# DataBreak.net
KiCad netlist of a schematic drawn in EAGLE
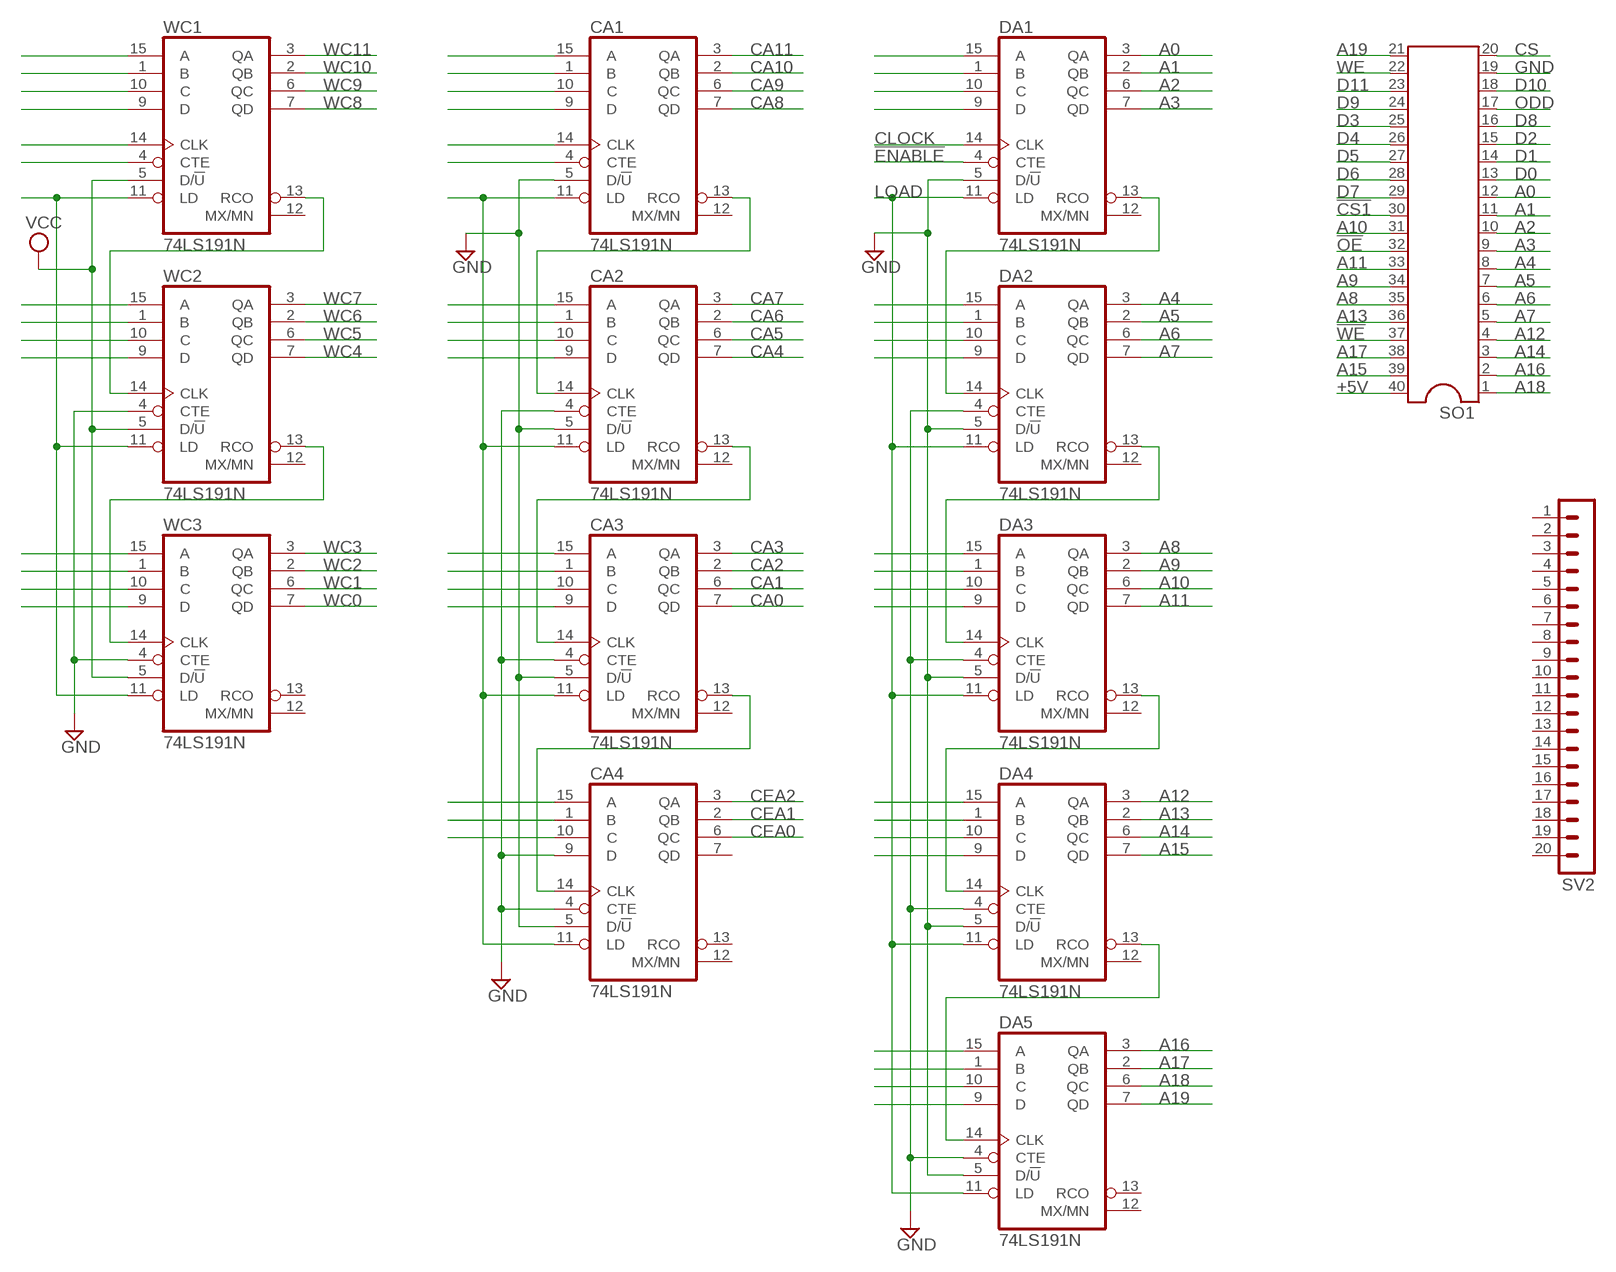
[diagram p0: schematic, sheet 1]

(export (version "E")
  (design (tool "Eeschema 10.0.6"))
  (components
    (comp (ref "CA1")
      (value "74LS191N")
      (footprint "eagle-import:DIL16")
      (libsource (lib "eagle-import") (part "74190NLS"))
    )
    (comp (ref "CA2")
      (value "74LS191N")
      (footprint "eagle-import:DIL16")
      (libsource (lib "eagle-import") (part "74190NLS"))
    )
    (comp (ref "CA3")
      (value "74LS191N")
      (footprint "eagle-import:DIL16")
      (libsource (lib "eagle-import") (part "74190NLS"))
    )
    (comp (ref "CA4")
      (value "74LS191N")
      (footprint "eagle-import:DIL16")
      (libsource (lib "eagle-import") (part "74190NLS"))
    )
    (comp (ref "DA1")
      (value "74LS191N")
      (footprint "eagle-import:DIL16")
      (libsource (lib "eagle-import") (part "74190NLS"))
    )
    (comp (ref "DA2")
      (value "74LS191N")
      (footprint "eagle-import:DIL16")
      (libsource (lib "eagle-import") (part "74190NLS"))
    )
    (comp (ref "DA3")
      (value "74LS191N")
      (footprint "eagle-import:DIL16")
      (libsource (lib "eagle-import") (part "74190NLS"))
    )
    (comp (ref "DA4")
      (value "74LS191N")
      (footprint "eagle-import:DIL16")
      (libsource (lib "eagle-import") (part "74190NLS"))
    )
    (comp (ref "DA5")
      (value "74LS191N")
      (footprint "eagle-import:DIL16")
      (libsource (lib "eagle-import") (part "74190NLS"))
    )
    (comp (ref "SO1")
      (value "DIL40")
      (footprint "eagle-import:DIL40")
      (libsource (lib "eagle-import") (part "DIL40"))
    )
    (comp (ref "SV2")
      (value "MA20-1L")
      (footprint "eagle-import:MA20-1L")
      (libsource (lib "eagle-import") (part "MA20-1L"))
    )
    (comp (ref "WC1")
      (value "74LS191N")
      (footprint "eagle-import:DIL16")
      (libsource (lib "eagle-import") (part "74190NLS"))
    )
    (comp (ref "WC2")
      (value "74LS191N")
      (footprint "eagle-import:DIL16")
      (libsource (lib "eagle-import") (part "74190NLS"))
    )
    (comp (ref "WC3")
      (value "74LS191N")
      (footprint "eagle-import:DIL16")
      (libsource (lib "eagle-import") (part "74190NLS"))
    )
  )
  (nets
    (net (code "1") (name "/+5V") (class "Default")
      (node (ref "SO1") (pin "40") (pinfunction "40_40") (pintype "passive"))
    )
    (net (code "2") (name "/A0") (class "Default")
      (node (ref "DA1") (pin "3") (pinfunction "QA_3") (pintype "output"))
      (node (ref "SO1") (pin "12") (pinfunction "12_12") (pintype "passive"))
    )
    (net (code "3") (name "/A1") (class "Default")
      (node (ref "DA1") (pin "2") (pinfunction "QB_2") (pintype "output"))
      (node (ref "SO1") (pin "11") (pinfunction "11_11") (pintype "passive"))
    )
    (net (code "4") (name "/A2") (class "Default")
      (node (ref "DA1") (pin "6") (pinfunction "QC_6") (pintype "output"))
      (node (ref "SO1") (pin "10") (pinfunction "10_10") (pintype "passive"))
    )
    (net (code "5") (name "/A3") (class "Default")
      (node (ref "DA1") (pin "7") (pinfunction "QD_7") (pintype "output"))
      (node (ref "SO1") (pin "9") (pinfunction "9_9") (pintype "passive"))
    )
    (net (code "6") (name "/A4") (class "Default")
      (node (ref "DA2") (pin "3") (pinfunction "QA_3") (pintype "output"))
      (node (ref "SO1") (pin "8") (pinfunction "8_8") (pintype "passive"))
    )
    (net (code "7") (name "/A5") (class "Default")
      (node (ref "DA2") (pin "2") (pinfunction "QB_2") (pintype "output"))
      (node (ref "SO1") (pin "7") (pinfunction "7_7") (pintype "passive"))
    )
    (net (code "8") (name "/A6") (class "Default")
      (node (ref "DA2") (pin "6") (pinfunction "QC_6") (pintype "output"))
      (node (ref "SO1") (pin "6") (pinfunction "6_6") (pintype "passive"))
    )
    (net (code "9") (name "/A7") (class "Default")
      (node (ref "DA2") (pin "7") (pinfunction "QD_7") (pintype "output"))
      (node (ref "SO1") (pin "5") (pinfunction "5_5") (pintype "passive"))
    )
    (net (code "10") (name "/A8") (class "Default")
      (node (ref "DA3") (pin "3") (pinfunction "QA_3") (pintype "output"))
      (node (ref "SO1") (pin "35") (pinfunction "35_35") (pintype "passive"))
    )
    (net (code "11") (name "/A9") (class "Default")
      (node (ref "DA3") (pin "2") (pinfunction "QB_2") (pintype "output"))
      (node (ref "SO1") (pin "34") (pinfunction "34_34") (pintype "passive"))
    )
    (net (code "12") (name "/A10") (class "Default")
      (node (ref "DA3") (pin "6") (pinfunction "QC_6") (pintype "output"))
      (node (ref "SO1") (pin "31") (pinfunction "31_31") (pintype "passive"))
    )
    (net (code "13") (name "/A11") (class "Default")
      (node (ref "DA3") (pin "7") (pinfunction "QD_7") (pintype "output"))
      (node (ref "SO1") (pin "33") (pinfunction "33_33") (pintype "passive"))
    )
    (net (code "14") (name "/A12") (class "Default")
      (node (ref "DA4") (pin "3") (pinfunction "QA_3") (pintype "output"))
      (node (ref "SO1") (pin "4") (pinfunction "4_4") (pintype "passive"))
    )
    (net (code "15") (name "/A13") (class "Default")
      (node (ref "DA4") (pin "2") (pinfunction "QB_2") (pintype "output"))
      (node (ref "SO1") (pin "36") (pinfunction "36_36") (pintype "passive"))
    )
    (net (code "16") (name "/A14") (class "Default")
      (node (ref "DA4") (pin "6") (pinfunction "QC_6") (pintype "output"))
      (node (ref "SO1") (pin "3") (pinfunction "3_3") (pintype "passive"))
    )
    (net (code "17") (name "/A15") (class "Default")
      (node (ref "DA4") (pin "7") (pinfunction "QD_7") (pintype "output"))
      (node (ref "SO1") (pin "39") (pinfunction "39_39") (pintype "passive"))
    )
    (net (code "18") (name "/A16") (class "Default")
      (node (ref "DA5") (pin "3") (pinfunction "QA_3") (pintype "output"))
      (node (ref "SO1") (pin "2") (pinfunction "2_2") (pintype "passive"))
    )
    (net (code "19") (name "/A17") (class "Default")
      (node (ref "DA5") (pin "2") (pinfunction "QB_2") (pintype "output"))
      (node (ref "SO1") (pin "38") (pinfunction "38_38") (pintype "passive"))
    )
    (net (code "20") (name "/A18") (class "Default")
      (node (ref "DA5") (pin "6") (pinfunction "QC_6") (pintype "output"))
      (node (ref "SO1") (pin "1") (pinfunction "1_1") (pintype "passive"))
    )
    (net (code "21") (name "/A19") (class "Default")
      (node (ref "DA5") (pin "7") (pinfunction "QD_7") (pintype "output"))
      (node (ref "SO1") (pin "21") (pinfunction "21_21") (pintype "passive"))
    )
    (net (code "22") (name "/CA0") (class "Default")
      (node (ref "CA3") (pin "7") (pinfunction "QD_7") (pintype "output"))
    )
    (net (code "23") (name "/CA1") (class "Default")
      (node (ref "CA3") (pin "6") (pinfunction "QC_6") (pintype "output"))
    )
    (net (code "24") (name "/CA2") (class "Default")
      (node (ref "CA3") (pin "2") (pinfunction "QB_2") (pintype "output"))
    )
    (net (code "25") (name "/CA3") (class "Default")
      (node (ref "CA3") (pin "3") (pinfunction "QA_3") (pintype "output"))
    )
    (net (code "26") (name "/CA4") (class "Default")
      (node (ref "CA2") (pin "7") (pinfunction "QD_7") (pintype "output"))
    )
    (net (code "27") (name "/CA5") (class "Default")
      (node (ref "CA2") (pin "6") (pinfunction "QC_6") (pintype "output"))
    )
    (net (code "28") (name "/CA6") (class "Default")
      (node (ref "CA2") (pin "2") (pinfunction "QB_2") (pintype "output"))
    )
    (net (code "29") (name "/CA7") (class "Default")
      (node (ref "CA2") (pin "3") (pinfunction "QA_3") (pintype "output"))
    )
    (net (code "30") (name "/CA8") (class "Default")
      (node (ref "CA1") (pin "7") (pinfunction "QD_7") (pintype "output"))
    )
    (net (code "31") (name "/CA9") (class "Default")
      (node (ref "CA1") (pin "6") (pinfunction "QC_6") (pintype "output"))
    )
    (net (code "32") (name "/CA10") (class "Default")
      (node (ref "CA1") (pin "2") (pinfunction "QB_2") (pintype "output"))
    )
    (net (code "33") (name "/CA11") (class "Default")
      (node (ref "CA1") (pin "3") (pinfunction "QA_3") (pintype "output"))
    )
    (net (code "34") (name "/CEA0") (class "Default")
      (node (ref "CA4") (pin "6") (pinfunction "QC_6") (pintype "output"))
    )
    (net (code "35") (name "/CEA1") (class "Default")
      (node (ref "CA4") (pin "2") (pinfunction "QB_2") (pintype "output"))
    )
    (net (code "36") (name "/CEA2") (class "Default")
      (node (ref "CA4") (pin "3") (pinfunction "QA_3") (pintype "output"))
    )
    (net (code "37") (name "/CLOCK") (class "Default")
      (node (ref "DA1") (pin "14") (pinfunction "CLK_14") (pintype "input"))
    )
    (net (code "38") (name "/CS") (class "Default")
      (node (ref "SO1") (pin "20") (pinfunction "20_20") (pintype "passive"))
    )
    (net (code "39") (name "/D0") (class "Default")
      (node (ref "SO1") (pin "13") (pinfunction "13_13") (pintype "passive"))
    )
    (net (code "40") (name "/D1") (class "Default")
      (node (ref "SO1") (pin "14") (pinfunction "14_14") (pintype "passive"))
    )
    (net (code "41") (name "/D2") (class "Default")
      (node (ref "SO1") (pin "15") (pinfunction "15_15") (pintype "passive"))
    )
    (net (code "42") (name "/D3") (class "Default")
      (node (ref "SO1") (pin "25") (pinfunction "25_25") (pintype "passive"))
    )
    (net (code "43") (name "/D4") (class "Default")
      (node (ref "SO1") (pin "26") (pinfunction "26_26") (pintype "passive"))
    )
    (net (code "44") (name "/D5") (class "Default")
      (node (ref "SO1") (pin "27") (pinfunction "27_27") (pintype "passive"))
    )
    (net (code "45") (name "/D6") (class "Default")
      (node (ref "SO1") (pin "28") (pinfunction "28_28") (pintype "passive"))
    )
    (net (code "46") (name "/D7") (class "Default")
      (node (ref "SO1") (pin "29") (pinfunction "29_29") (pintype "passive"))
    )
    (net (code "47") (name "/D8") (class "Default")
      (node (ref "SO1") (pin "16") (pinfunction "16_16") (pintype "passive"))
    )
    (net (code "48") (name "/D9") (class "Default")
      (node (ref "SO1") (pin "24") (pinfunction "24_24") (pintype "passive"))
    )
    (net (code "49") (name "/D10") (class "Default")
      (node (ref "SO1") (pin "18") (pinfunction "18_18") (pintype "passive"))
    )
    (net (code "50") (name "/D11") (class "Default")
      (node (ref "SO1") (pin "23") (pinfunction "23_23") (pintype "passive"))
    )
    (net (code "51") (name "/LOAD") (class "Default")
      (node (ref "DA1") (pin "11") (pinfunction "LD_11") (pintype "input"))
      (node (ref "DA2") (pin "11") (pinfunction "LD_11") (pintype "input"))
      (node (ref "DA3") (pin "11") (pinfunction "LD_11") (pintype "input"))
      (node (ref "DA4") (pin "11") (pinfunction "LD_11") (pintype "input"))
      (node (ref "DA5") (pin "11") (pinfunction "LD_11") (pintype "input"))
    )
    (net (code "52") (name "/ODD") (class "Default")
      (node (ref "SO1") (pin "17") (pinfunction "17_17") (pintype "passive"))
    )
    (net (code "53") (name "/WC0") (class "Default")
      (node (ref "WC3") (pin "7") (pinfunction "QD_7") (pintype "output"))
    )
    (net (code "54") (name "/WC1") (class "Default")
      (node (ref "WC3") (pin "6") (pinfunction "QC_6") (pintype "output"))
    )
    (net (code "55") (name "/WC2") (class "Default")
      (node (ref "WC3") (pin "2") (pinfunction "QB_2") (pintype "output"))
    )
    (net (code "56") (name "/WC3") (class "Default")
      (node (ref "WC3") (pin "3") (pinfunction "QA_3") (pintype "output"))
    )
    (net (code "57") (name "/WC4") (class "Default")
      (node (ref "WC2") (pin "7") (pinfunction "QD_7") (pintype "output"))
    )
    (net (code "58") (name "/WC5") (class "Default")
      (node (ref "WC2") (pin "6") (pinfunction "QC_6") (pintype "output"))
    )
    (net (code "59") (name "/WC6") (class "Default")
      (node (ref "WC2") (pin "2") (pinfunction "QB_2") (pintype "output"))
    )
    (net (code "60") (name "/WC7") (class "Default")
      (node (ref "WC2") (pin "3") (pinfunction "QA_3") (pintype "output"))
    )
    (net (code "61") (name "/WC8") (class "Default")
      (node (ref "WC1") (pin "7") (pinfunction "QD_7") (pintype "output"))
    )
    (net (code "62") (name "/WC9") (class "Default")
      (node (ref "WC1") (pin "6") (pinfunction "QC_6") (pintype "output"))
    )
    (net (code "63") (name "/WC10") (class "Default")
      (node (ref "WC1") (pin "2") (pinfunction "QB_2") (pintype "output"))
    )
    (net (code "64") (name "/WC11") (class "Default")
      (node (ref "WC1") (pin "3") (pinfunction "QA_3") (pintype "output"))
    )
    (net (code "65") (name "/WE") (class "Default")
      (node (ref "SO1") (pin "22") (pinfunction "22_22") (pintype "passive"))
    )
    (net (code "66") (name "/~{CS1}") (class "Default")
      (node (ref "SO1") (pin "30") (pinfunction "30_30") (pintype "passive"))
    )
    (net (code "67") (name "/~{ENABLE}") (class "Default")
      (node (ref "DA1") (pin "4") (pinfunction "CTE_4") (pintype "input"))
    )
    (net (code "68") (name "/~{OE}") (class "Default")
      (node (ref "SO1") (pin "32") (pinfunction "32_32") (pintype "passive"))
    )
    (net (code "69") (name "/~{WE}") (class "Default")
      (node (ref "SO1") (pin "37") (pinfunction "37_37") (pintype "passive"))
    )
    (net (code "70") (name "GND") (class "Default")
      (node (ref "CA1") (pin "5") (pinfunction "D/~{U}_5") (pintype "input"))
      (node (ref "CA2") (pin "4") (pinfunction "CTE_4") (pintype "input"))
      (node (ref "CA2") (pin "5") (pinfunction "D/~{U}_5") (pintype "input"))
      (node (ref "CA3") (pin "4") (pinfunction "CTE_4") (pintype "input"))
      (node (ref "CA3") (pin "5") (pinfunction "D/~{U}_5") (pintype "input"))
      (node (ref "CA4") (pin "4") (pinfunction "CTE_4") (pintype "input"))
      (node (ref "CA4") (pin "5") (pinfunction "D/~{U}_5") (pintype "input"))
      (node (ref "CA4") (pin "9") (pinfunction "D_9") (pintype "input"))
      (node (ref "DA1") (pin "5") (pinfunction "D/~{U}_5") (pintype "input"))
      (node (ref "DA2") (pin "4") (pinfunction "CTE_4") (pintype "input"))
      (node (ref "DA2") (pin "5") (pinfunction "D/~{U}_5") (pintype "input"))
      (node (ref "DA3") (pin "4") (pinfunction "CTE_4") (pintype "input"))
      (node (ref "DA3") (pin "5") (pinfunction "D/~{U}_5") (pintype "input"))
      (node (ref "DA4") (pin "4") (pinfunction "CTE_4") (pintype "input"))
      (node (ref "DA4") (pin "5") (pinfunction "D/~{U}_5") (pintype "input"))
      (node (ref "DA5") (pin "4") (pinfunction "CTE_4") (pintype "input"))
      (node (ref "DA5") (pin "5") (pinfunction "D/~{U}_5") (pintype "input"))
      (node (ref "SO1") (pin "19") (pinfunction "19_19") (pintype "passive"))
      (node (ref "WC2") (pin "4") (pinfunction "CTE_4") (pintype "input"))
      (node (ref "WC3") (pin "4") (pinfunction "CTE_4") (pintype "input"))
    )
    (net (code "71") (name "Net-(CA1A-LD)") (class "Default")
      (node (ref "CA1") (pin "11") (pinfunction "LD_11") (pintype "input"))
      (node (ref "CA2") (pin "11") (pinfunction "LD_11") (pintype "input"))
      (node (ref "CA3") (pin "11") (pinfunction "LD_11") (pintype "input"))
      (node (ref "CA4") (pin "11") (pinfunction "LD_11") (pintype "input"))
    )
    (net (code "72") (name "Net-(CA1A-RCO)") (class "Default")
      (node (ref "CA1") (pin "13") (pinfunction "RCO_13") (pintype "output"))
      (node (ref "CA2") (pin "14") (pinfunction "CLK_14") (pintype "input"))
    )
    (net (code "73") (name "Net-(CA2A-RCO)") (class "Default")
      (node (ref "CA2") (pin "13") (pinfunction "RCO_13") (pintype "output"))
      (node (ref "CA3") (pin "14") (pinfunction "CLK_14") (pintype "input"))
    )
    (net (code "74") (name "Net-(CA3A-RCO)") (class "Default")
      (node (ref "CA3") (pin "13") (pinfunction "RCO_13") (pintype "output"))
      (node (ref "CA4") (pin "14") (pinfunction "CLK_14") (pintype "input"))
    )
    (net (code "75") (name "Net-(DA1A-RCO)") (class "Default")
      (node (ref "DA1") (pin "13") (pinfunction "RCO_13") (pintype "output"))
      (node (ref "DA2") (pin "14") (pinfunction "CLK_14") (pintype "input"))
    )
    (net (code "76") (name "Net-(DA2A-RCO)") (class "Default")
      (node (ref "DA2") (pin "13") (pinfunction "RCO_13") (pintype "output"))
      (node (ref "DA3") (pin "14") (pinfunction "CLK_14") (pintype "input"))
    )
    (net (code "77") (name "Net-(DA3A-RCO)") (class "Default")
      (node (ref "DA3") (pin "13") (pinfunction "RCO_13") (pintype "output"))
      (node (ref "DA4") (pin "14") (pinfunction "CLK_14") (pintype "input"))
    )
    (net (code "78") (name "Net-(DA4A-RCO)") (class "Default")
      (node (ref "DA4") (pin "13") (pinfunction "RCO_13") (pintype "output"))
      (node (ref "DA5") (pin "14") (pinfunction "CLK_14") (pintype "input"))
    )
    (net (code "79") (name "Net-(WC1A-LD)") (class "Default")
      (node (ref "WC1") (pin "11") (pinfunction "LD_11") (pintype "input"))
      (node (ref "WC2") (pin "11") (pinfunction "LD_11") (pintype "input"))
      (node (ref "WC3") (pin "11") (pinfunction "LD_11") (pintype "input"))
    )
    (net (code "80") (name "Net-(WC1A-RCO)") (class "Default")
      (node (ref "WC1") (pin "13") (pinfunction "RCO_13") (pintype "output"))
      (node (ref "WC2") (pin "14") (pinfunction "CLK_14") (pintype "input"))
    )
    (net (code "81") (name "Net-(WC2A-RCO)") (class "Default")
      (node (ref "WC2") (pin "13") (pinfunction "RCO_13") (pintype "output"))
      (node (ref "WC3") (pin "14") (pinfunction "CLK_14") (pintype "input"))
    )
    (net (code "82") (name "VCC") (class "Default")
      (node (ref "WC1") (pin "5") (pinfunction "D/~{U}_5") (pintype "input"))
      (node (ref "WC2") (pin "5") (pinfunction "D/~{U}_5") (pintype "input"))
      (node (ref "WC3") (pin "5") (pinfunction "D/~{U}_5") (pintype "input"))
    )
    (net (code "83") (name "unconnected-(CA1A-A-Pad15)") (class "Default")
      (node (ref "CA1") (pin "15") (pinfunction "A_15") (pintype "input"))
    )
    (net (code "84") (name "unconnected-(CA1A-B-Pad1)") (class "Default")
      (node (ref "CA1") (pin "1") (pinfunction "B_1") (pintype "input"))
    )
    (net (code "85") (name "unconnected-(CA1A-C-Pad10)") (class "Default")
      (node (ref "CA1") (pin "10") (pinfunction "C_10") (pintype "input"))
    )
    (net (code "86") (name "unconnected-(CA1A-CLK-Pad14)") (class "Default")
      (node (ref "CA1") (pin "14") (pinfunction "CLK_14") (pintype "input"))
    )
    (net (code "87") (name "unconnected-(CA1A-CTE-Pad4)") (class "Default")
      (node (ref "CA1") (pin "4") (pinfunction "CTE_4") (pintype "input"))
    )
    (net (code "88") (name "unconnected-(CA1A-D-Pad9)") (class "Default")
      (node (ref "CA1") (pin "9") (pinfunction "D_9") (pintype "input"))
    )
    (net (code "89") (name "unconnected-(CA1A-MX{slash}MN-Pad12)") (class "Default")
      (node (ref "CA1") (pin "12") (pinfunction "MX/MN_12") (pintype "output"))
    )
    (net (code "90") (name "unconnected-(CA2A-A-Pad15)") (class "Default")
      (node (ref "CA2") (pin "15") (pinfunction "A_15") (pintype "input"))
    )
    (net (code "91") (name "unconnected-(CA2A-B-Pad1)") (class "Default")
      (node (ref "CA2") (pin "1") (pinfunction "B_1") (pintype "input"))
    )
    (net (code "92") (name "unconnected-(CA2A-C-Pad10)") (class "Default")
      (node (ref "CA2") (pin "10") (pinfunction "C_10") (pintype "input"))
    )
    (net (code "93") (name "unconnected-(CA2A-D-Pad9)") (class "Default")
      (node (ref "CA2") (pin "9") (pinfunction "D_9") (pintype "input"))
    )
    (net (code "94") (name "unconnected-(CA2A-MX{slash}MN-Pad12)") (class "Default")
      (node (ref "CA2") (pin "12") (pinfunction "MX/MN_12") (pintype "output"))
    )
    (net (code "95") (name "unconnected-(CA3A-A-Pad15)") (class "Default")
      (node (ref "CA3") (pin "15") (pinfunction "A_15") (pintype "input"))
    )
    (net (code "96") (name "unconnected-(CA3A-B-Pad1)") (class "Default")
      (node (ref "CA3") (pin "1") (pinfunction "B_1") (pintype "input"))
    )
    (net (code "97") (name "unconnected-(CA3A-C-Pad10)") (class "Default")
      (node (ref "CA3") (pin "10") (pinfunction "C_10") (pintype "input"))
    )
    (net (code "98") (name "unconnected-(CA3A-D-Pad9)") (class "Default")
      (node (ref "CA3") (pin "9") (pinfunction "D_9") (pintype "input"))
    )
    (net (code "99") (name "unconnected-(CA3A-MX{slash}MN-Pad12)") (class "Default")
      (node (ref "CA3") (pin "12") (pinfunction "MX/MN_12") (pintype "output"))
    )
    (net (code "100") (name "unconnected-(CA4A-A-Pad15)") (class "Default")
      (node (ref "CA4") (pin "15") (pinfunction "A_15") (pintype "input"))
    )
    (net (code "101") (name "unconnected-(CA4A-B-Pad1)") (class "Default")
      (node (ref "CA4") (pin "1") (pinfunction "B_1") (pintype "input"))
    )
    (net (code "102") (name "unconnected-(CA4A-C-Pad10)") (class "Default")
      (node (ref "CA4") (pin "10") (pinfunction "C_10") (pintype "input"))
    )
    (net (code "103") (name "unconnected-(CA4A-MX{slash}MN-Pad12)") (class "Default")
      (node (ref "CA4") (pin "12") (pinfunction "MX/MN_12") (pintype "output"))
    )
    (net (code "104") (name "unconnected-(CA4A-QD-Pad7)") (class "Default")
      (node (ref "CA4") (pin "7") (pinfunction "QD_7") (pintype "output"))
    )
    (net (code "105") (name "unconnected-(CA4A-RCO-Pad13)") (class "Default")
      (node (ref "CA4") (pin "13") (pinfunction "RCO_13") (pintype "output"))
    )
    (net (code "106") (name "unconnected-(DA1A-A-Pad15)") (class "Default")
      (node (ref "DA1") (pin "15") (pinfunction "A_15") (pintype "input"))
    )
    (net (code "107") (name "unconnected-(DA1A-B-Pad1)") (class "Default")
      (node (ref "DA1") (pin "1") (pinfunction "B_1") (pintype "input"))
    )
    (net (code "108") (name "unconnected-(DA1A-C-Pad10)") (class "Default")
      (node (ref "DA1") (pin "10") (pinfunction "C_10") (pintype "input"))
    )
    (net (code "109") (name "unconnected-(DA1A-D-Pad9)") (class "Default")
      (node (ref "DA1") (pin "9") (pinfunction "D_9") (pintype "input"))
    )
    (net (code "110") (name "unconnected-(DA1A-MX{slash}MN-Pad12)") (class "Default")
      (node (ref "DA1") (pin "12") (pinfunction "MX/MN_12") (pintype "output"))
    )
    (net (code "111") (name "unconnected-(DA2A-A-Pad15)") (class "Default")
      (node (ref "DA2") (pin "15") (pinfunction "A_15") (pintype "input"))
    )
    (net (code "112") (name "unconnected-(DA2A-B-Pad1)") (class "Default")
      (node (ref "DA2") (pin "1") (pinfunction "B_1") (pintype "input"))
    )
    (net (code "113") (name "unconnected-(DA2A-C-Pad10)") (class "Default")
      (node (ref "DA2") (pin "10") (pinfunction "C_10") (pintype "input"))
    )
    (net (code "114") (name "unconnected-(DA2A-D-Pad9)") (class "Default")
      (node (ref "DA2") (pin "9") (pinfunction "D_9") (pintype "input"))
    )
    (net (code "115") (name "unconnected-(DA2A-MX{slash}MN-Pad12)") (class "Default")
      (node (ref "DA2") (pin "12") (pinfunction "MX/MN_12") (pintype "output"))
    )
    (net (code "116") (name "unconnected-(DA3A-A-Pad15)") (class "Default")
      (node (ref "DA3") (pin "15") (pinfunction "A_15") (pintype "input"))
    )
    (net (code "117") (name "unconnected-(DA3A-B-Pad1)") (class "Default")
      (node (ref "DA3") (pin "1") (pinfunction "B_1") (pintype "input"))
    )
    (net (code "118") (name "unconnected-(DA3A-C-Pad10)") (class "Default")
      (node (ref "DA3") (pin "10") (pinfunction "C_10") (pintype "input"))
    )
    (net (code "119") (name "unconnected-(DA3A-D-Pad9)") (class "Default")
      (node (ref "DA3") (pin "9") (pinfunction "D_9") (pintype "input"))
    )
    (net (code "120") (name "unconnected-(DA3A-MX{slash}MN-Pad12)") (class "Default")
      (node (ref "DA3") (pin "12") (pinfunction "MX/MN_12") (pintype "output"))
    )
    (net (code "121") (name "unconnected-(DA4A-A-Pad15)") (class "Default")
      (node (ref "DA4") (pin "15") (pinfunction "A_15") (pintype "input"))
    )
    (net (code "122") (name "unconnected-(DA4A-B-Pad1)") (class "Default")
      (node (ref "DA4") (pin "1") (pinfunction "B_1") (pintype "input"))
    )
    (net (code "123") (name "unconnected-(DA4A-C-Pad10)") (class "Default")
      (node (ref "DA4") (pin "10") (pinfunction "C_10") (pintype "input"))
    )
    (net (code "124") (name "unconnected-(DA4A-D-Pad9)") (class "Default")
      (node (ref "DA4") (pin "9") (pinfunction "D_9") (pintype "input"))
    )
    (net (code "125") (name "unconnected-(DA4A-MX{slash}MN-Pad12)") (class "Default")
      (node (ref "DA4") (pin "12") (pinfunction "MX/MN_12") (pintype "output"))
    )
    (net (code "126") (name "unconnected-(DA5A-A-Pad15)") (class "Default")
      (node (ref "DA5") (pin "15") (pinfunction "A_15") (pintype "input"))
    )
    (net (code "127") (name "unconnected-(DA5A-B-Pad1)") (class "Default")
      (node (ref "DA5") (pin "1") (pinfunction "B_1") (pintype "input"))
    )
    (net (code "128") (name "unconnected-(DA5A-C-Pad10)") (class "Default")
      (node (ref "DA5") (pin "10") (pinfunction "C_10") (pintype "input"))
    )
    (net (code "129") (name "unconnected-(DA5A-D-Pad9)") (class "Default")
      (node (ref "DA5") (pin "9") (pinfunction "D_9") (pintype "input"))
    )
    (net (code "130") (name "unconnected-(DA5A-MX{slash}MN-Pad12)") (class "Default")
      (node (ref "DA5") (pin "12") (pinfunction "MX/MN_12") (pintype "output"))
    )
    (net (code "131") (name "unconnected-(DA5A-RCO-Pad13)") (class "Default")
      (node (ref "DA5") (pin "13") (pinfunction "RCO_13") (pintype "output"))
    )
    (net (code "132") (name "unconnected-(SV2-Pad1)") (class "Default")
      (node (ref "SV2") (pin "1") (pinfunction "1_1") (pintype "passive"))
    )
    (net (code "133") (name "unconnected-(SV2-Pad2)") (class "Default")
      (node (ref "SV2") (pin "2") (pinfunction "2_2") (pintype "passive"))
    )
    (net (code "134") (name "unconnected-(SV2-Pad3)") (class "Default")
      (node (ref "SV2") (pin "3") (pinfunction "3_3") (pintype "passive"))
    )
    (net (code "135") (name "unconnected-(SV2-Pad4)") (class "Default")
      (node (ref "SV2") (pin "4") (pinfunction "4_4") (pintype "passive"))
    )
    (net (code "136") (name "unconnected-(SV2-Pad5)") (class "Default")
      (node (ref "SV2") (pin "5") (pinfunction "5_5") (pintype "passive"))
    )
    (net (code "137") (name "unconnected-(SV2-Pad6)") (class "Default")
      (node (ref "SV2") (pin "6") (pinfunction "6_6") (pintype "passive"))
    )
    (net (code "138") (name "unconnected-(SV2-Pad7)") (class "Default")
      (node (ref "SV2") (pin "7") (pinfunction "7_7") (pintype "passive"))
    )
    (net (code "139") (name "unconnected-(SV2-Pad8)") (class "Default")
      (node (ref "SV2") (pin "8") (pinfunction "8_8") (pintype "passive"))
    )
    (net (code "140") (name "unconnected-(SV2-Pad9)") (class "Default")
      (node (ref "SV2") (pin "9") (pinfunction "9_9") (pintype "passive"))
    )
    (net (code "141") (name "unconnected-(SV2-Pad10)") (class "Default")
      (node (ref "SV2") (pin "10") (pinfunction "10_10") (pintype "passive"))
    )
    (net (code "142") (name "unconnected-(SV2-Pad11)") (class "Default")
      (node (ref "SV2") (pin "11") (pinfunction "11_11") (pintype "passive"))
    )
    (net (code "143") (name "unconnected-(SV2-Pad12)") (class "Default")
      (node (ref "SV2") (pin "12") (pinfunction "12_12") (pintype "passive"))
    )
    (net (code "144") (name "unconnected-(SV2-Pad13)") (class "Default")
      (node (ref "SV2") (pin "13") (pinfunction "13_13") (pintype "passive"))
    )
    (net (code "145") (name "unconnected-(SV2-Pad14)") (class "Default")
      (node (ref "SV2") (pin "14") (pinfunction "14_14") (pintype "passive"))
    )
    (net (code "146") (name "unconnected-(SV2-Pad15)") (class "Default")
      (node (ref "SV2") (pin "15") (pinfunction "15_15") (pintype "passive"))
    )
    (net (code "147") (name "unconnected-(SV2-Pad16)") (class "Default")
      (node (ref "SV2") (pin "16") (pinfunction "16_16") (pintype "passive"))
    )
    (net (code "148") (name "unconnected-(SV2-Pad17)") (class "Default")
      (node (ref "SV2") (pin "17") (pinfunction "17_17") (pintype "passive"))
    )
    (net (code "149") (name "unconnected-(SV2-Pad18)") (class "Default")
      (node (ref "SV2") (pin "18") (pinfunction "18_18") (pintype "passive"))
    )
    (net (code "150") (name "unconnected-(SV2-Pad19)") (class "Default")
      (node (ref "SV2") (pin "19") (pinfunction "19_19") (pintype "passive"))
    )
    (net (code "151") (name "unconnected-(SV2-Pad20)") (class "Default")
      (node (ref "SV2") (pin "20") (pinfunction "20_20") (pintype "passive"))
    )
    (net (code "152") (name "unconnected-(WC1A-A-Pad15)") (class "Default")
      (node (ref "WC1") (pin "15") (pinfunction "A_15") (pintype "input"))
    )
    (net (code "153") (name "unconnected-(WC1A-B-Pad1)") (class "Default")
      (node (ref "WC1") (pin "1") (pinfunction "B_1") (pintype "input"))
    )
    (net (code "154") (name "unconnected-(WC1A-C-Pad10)") (class "Default")
      (node (ref "WC1") (pin "10") (pinfunction "C_10") (pintype "input"))
    )
    (net (code "155") (name "unconnected-(WC1A-CLK-Pad14)") (class "Default")
      (node (ref "WC1") (pin "14") (pinfunction "CLK_14") (pintype "input"))
    )
    (net (code "156") (name "unconnected-(WC1A-CTE-Pad4)") (class "Default")
      (node (ref "WC1") (pin "4") (pinfunction "CTE_4") (pintype "input"))
    )
    (net (code "157") (name "unconnected-(WC1A-D-Pad9)") (class "Default")
      (node (ref "WC1") (pin "9") (pinfunction "D_9") (pintype "input"))
    )
    (net (code "158") (name "unconnected-(WC1A-MX{slash}MN-Pad12)") (class "Default")
      (node (ref "WC1") (pin "12") (pinfunction "MX/MN_12") (pintype "output"))
    )
    (net (code "159") (name "unconnected-(WC2A-A-Pad15)") (class "Default")
      (node (ref "WC2") (pin "15") (pinfunction "A_15") (pintype "input"))
    )
    (net (code "160") (name "unconnected-(WC2A-B-Pad1)") (class "Default")
      (node (ref "WC2") (pin "1") (pinfunction "B_1") (pintype "input"))
    )
    (net (code "161") (name "unconnected-(WC2A-C-Pad10)") (class "Default")
      (node (ref "WC2") (pin "10") (pinfunction "C_10") (pintype "input"))
    )
    (net (code "162") (name "unconnected-(WC2A-D-Pad9)") (class "Default")
      (node (ref "WC2") (pin "9") (pinfunction "D_9") (pintype "input"))
    )
    (net (code "163") (name "unconnected-(WC2A-MX{slash}MN-Pad12)") (class "Default")
      (node (ref "WC2") (pin "12") (pinfunction "MX/MN_12") (pintype "output"))
    )
    (net (code "164") (name "unconnected-(WC3A-A-Pad15)") (class "Default")
      (node (ref "WC3") (pin "15") (pinfunction "A_15") (pintype "input"))
    )
    (net (code "165") (name "unconnected-(WC3A-B-Pad1)") (class "Default")
      (node (ref "WC3") (pin "1") (pinfunction "B_1") (pintype "input"))
    )
    (net (code "166") (name "unconnected-(WC3A-C-Pad10)") (class "Default")
      (node (ref "WC3") (pin "10") (pinfunction "C_10") (pintype "input"))
    )
    (net (code "167") (name "unconnected-(WC3A-D-Pad9)") (class "Default")
      (node (ref "WC3") (pin "9") (pinfunction "D_9") (pintype "input"))
    )
    (net (code "168") (name "unconnected-(WC3A-MX{slash}MN-Pad12)") (class "Default")
      (node (ref "WC3") (pin "12") (pinfunction "MX/MN_12") (pintype "output"))
    )
    (net (code "169") (name "unconnected-(WC3A-RCO-Pad13)") (class "Default")
      (node (ref "WC3") (pin "13") (pinfunction "RCO_13") (pintype "output"))
    )
  )
)
